# Power.net
KiCad netlist of a schematic drawn in Altium Designer
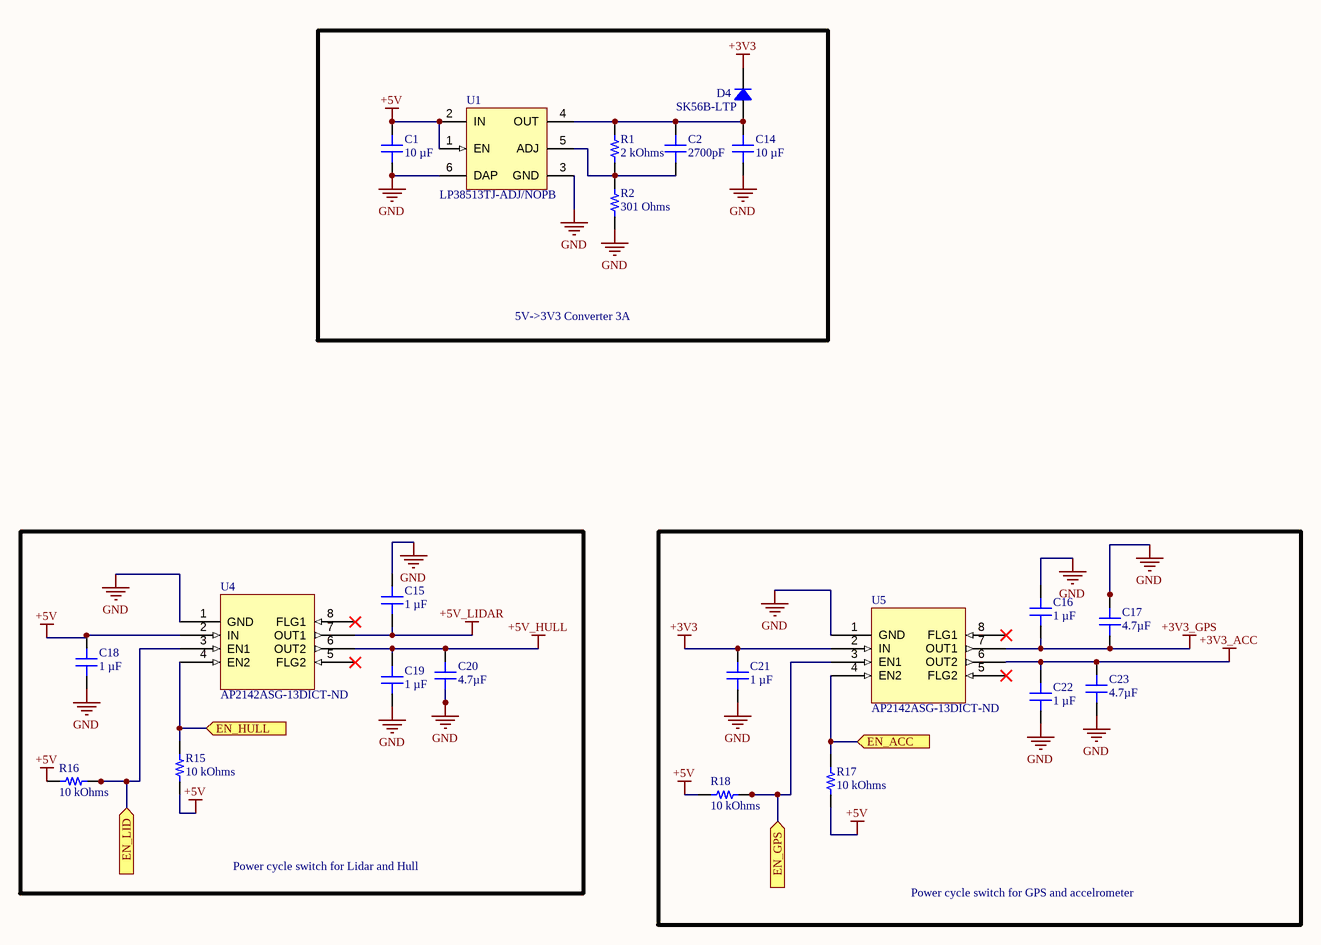
[diagram p0: Power.SchDoc]

(export (version "E")
  (design (tool "Eeschema 10.0.6"))
  (components
    (comp (ref "C1")
      (value "10 µF")
      (footprint "CAP 0805_2012")
      (description "CAP CER 10UF 16V X5R 0805")
      (fields
        (field (name "PART NUMBER") "CGA4J1X5R1C106K125AC")
        (field (name "MANUFACTURER") "TDK Corporation")
      )
      (libsource (lib "Celestial Altium Library - altium_library") (part "Capacitor"))
    )
    (comp (ref "C2")
      (value "2700pF")
      (footprint "CAP 0603_1608")
      (description "CAP CER 2700PF 50V X7R 0603")
      (fields (field (name "PART NUMBER") "06035C272KAT2A") (field (name "MANUFACTURER") "AVX Corporation"))
      (libsource (lib "Celestial Altium Library - altium_library") (part "Capacitor"))
    )
    (comp (ref "C14")
      (value "10 µF")
      (footprint "CAP 0805_2012")
      (description "CAP CER 10UF 16V X5R 0805")
      (fields
        (field (name "PART NUMBER") "CGA4J1X5R1C106K125AC")
        (field (name "MANUFACTURER") "TDK Corporation")
      )
      (libsource (lib "Celestial Altium Library - altium_library") (part "Capacitor"))
    )
    (comp (ref "C15")
      (value "1 µF")
      (footprint "CAP 0603_1608")
      (description "CAP CER 1UF 16V X7R 0603")
      (fields (field (name "PART NUMBER") "CM105X7R105K16ATH") (field (name "MANUFACTURER") "KYOCERA AVX"))
      (libsource (lib "Celestial Altium Library - altium_library") (part "Capacitor"))
    )
    (comp (ref "C16")
      (value "1 µF")
      (footprint "CAP 0603_1608")
      (description "CAP CER 1UF 16V X7R 0603")
      (fields (field (name "PART NUMBER") "CM105X7R105K16ATH") (field (name "MANUFACTURER") "KYOCERA AVX"))
      (libsource (lib "Celestial Altium Library - altium_library") (part "Capacitor"))
    )
    (comp (ref "C17")
      (value "4.7µF")
      (footprint "CAP 0805_2012")
      (description "CAP CER 4.7UF 10V X7R 0805")
      (fields (field (name "PART NUMBER") "0805ZC475MAT2A") (field (name "MANUFACTURER") "AVX Corporation"))
      (libsource (lib "Celestial Altium Library - altium_library") (part "Capacitor"))
    )
    (comp (ref "C18")
      (value "1 µF")
      (footprint "CAP 0603_1608")
      (description "CAP CER 1UF 16V X7R 0603")
      (fields (field (name "PART NUMBER") "CM105X7R105K16ATH") (field (name "MANUFACTURER") "KYOCERA AVX"))
      (libsource (lib "Celestial Altium Library - altium_library") (part "Capacitor"))
    )
    (comp (ref "C19")
      (value "1 µF")
      (footprint "CAP 0603_1608")
      (description "CAP CER 1UF 16V X7R 0603")
      (fields (field (name "PART NUMBER") "CM105X7R105K16ATH") (field (name "MANUFACTURER") "KYOCERA AVX"))
      (libsource (lib "Celestial Altium Library - altium_library") (part "Capacitor"))
    )
    (comp (ref "C20")
      (value "4.7µF")
      (footprint "CAP 0805_2012")
      (description "CAP CER 4.7UF 10V X7R 0805")
      (fields (field (name "PART NUMBER") "0805ZC475MAT2A") (field (name "MANUFACTURER") "AVX Corporation"))
      (libsource (lib "Celestial Altium Library - altium_library") (part "Capacitor"))
    )
    (comp (ref "C21")
      (value "1 µF")
      (footprint "CAP 0603_1608")
      (description "CAP CER 1UF 16V X7R 0603")
      (fields (field (name "PART NUMBER") "CM105X7R105K16ATH") (field (name "MANUFACTURER") "KYOCERA AVX"))
      (libsource (lib "Celestial Altium Library - altium_library") (part "Capacitor"))
    )
    (comp (ref "C22")
      (value "1 µF")
      (footprint "CAP 0603_1608")
      (description "CAP CER 1UF 16V X7R 0603")
      (fields (field (name "PART NUMBER") "CM105X7R105K16ATH") (field (name "MANUFACTURER") "KYOCERA AVX"))
      (libsource (lib "Celestial Altium Library - altium_library") (part "Capacitor"))
    )
    (comp (ref "C23")
      (value "4.7µF")
      (footprint "CAP 0805_2012")
      (description "CAP CER 4.7UF 10V X7R 0805")
      (fields (field (name "PART NUMBER") "0805ZC475MAT2A") (field (name "MANUFACTURER") "AVX Corporation"))
      (libsource (lib "Celestial Altium Library - altium_library") (part "Capacitor"))
    )
    (comp (ref "D4")
      (value "SK56B-LTP")
      (footprint "DO214AA SMB")
      (description "DIODE SCHOTTKY 60V 5A DO214AA")
      (fields (field (name "MANUFACTURER") "Micro Commercial Co"))
      (libsource (lib "Celestial Altium Library - altium_library") (part "Diode"))
    )
    (comp (ref "R1")
      (value "2 kOhms")
      (footprint "RES 0603_1608")
      (description "RES 2K OHM 1% 1/10W 0603")
      (fields
        (field (name "PART NUMBER") "RMCF0603FT2K00")
        (field (name "MANUFACTURER") "Stackpole Electronics Inc")
      )
      (libsource (lib "Celestial Altium Library - altium_library") (part "Resistor"))
    )
    (comp (ref "R2")
      (value "301 Ohms")
      (footprint "RES 0603_1608")
      (description "RES 301 OHM 1% 1/10W 0603")
      (fields
        (field (name "PART NUMBER") "RMCF0603FT301R")
        (field (name "MANUFACTURER") "Stackpole Electronics Inc")
      )
      (libsource (lib "Celestial Altium Library - altium_library") (part "Resistor"))
    )
    (comp (ref "R15")
      (value "10 kOhms")
      (footprint "RES 0603_1608")
      (description "RES SMD 10K OHM 1% 1/10W 0603")
      (fields (field (name "PART NUMBER") "RT0603FRE0710KL") (field (name "MANUFACTURER") "Yageo"))
      (libsource (lib "Celestial Altium Library - altium_library") (part "Resistor"))
    )
    (comp (ref "R16")
      (value "10 kOhms")
      (footprint "RES 0603_1608")
      (description "RES SMD 10K OHM 1% 1/10W 0603")
      (fields (field (name "PART NUMBER") "RT0603FRE0710KL") (field (name "MANUFACTURER") "Yageo"))
      (libsource (lib "Celestial Altium Library - altium_library") (part "Resistor"))
    )
    (comp (ref "R17")
      (value "10 kOhms")
      (footprint "RES 0603_1608")
      (description "RES SMD 10K OHM 1% 1/10W 0603")
      (fields (field (name "PART NUMBER") "RT0603FRE0710KL") (field (name "MANUFACTURER") "Yageo"))
      (libsource (lib "Celestial Altium Library - altium_library") (part "Resistor"))
    )
    (comp (ref "R18")
      (value "10 kOhms")
      (footprint "RES 0603_1608")
      (description "RES SMD 10K OHM 1% 1/10W 0603")
      (fields (field (name "PART NUMBER") "RT0603FRE0710KL") (field (name "MANUFACTURER") "Yageo"))
      (libsource (lib "Celestial Altium Library - altium_library") (part "Resistor"))
    )
    (comp (ref "U1")
      (value "LP38513TJ-ADJ/NOPB")
      (footprint "NDQ0005A_M")
      (fields (field (name "MANUFACTURER") "Texas Instruments"))
      (libsource (lib "Altium Content Vault") (part "PM-REG-LP38513-SIL6A"))
    )
    (comp (ref "U4")
      (value "AP2142ASG-13DICT-ND")
      (footprint "SOP127P600X175-8N")
      (description "AP2142A Series 5.5 V 0.5 A Dual Channel Current-Limited Power Switch - SOIC-8")
      (libsource (lib "Americas- Environmental Engineering Club- University of Victoria") (part "AP2142ASG-13DICT-ND-Symbol-1"))
    )
    (comp (ref "U5")
      (value "AP2142ASG-13DICT-ND")
      (footprint "SOP127P600X175-8N")
      (description "AP2142A Series 5.5 V 0.5 A Dual Channel Current-Limited Power Switch - SOIC-8")
      (libsource (lib "Americas- Environmental Engineering Club- University of Victoria") (part "AP2142ASG-13DICT-ND-Symbol-1"))
    )
  )
  (nets
    (net (code "1") (name "+3V3") (class "Default")
      (node (ref "C21") (pin "1") (pinfunction "1_1") (pintype "passive"))
      (node (ref "D4") (pin "2") (pinfunction "2_2") (pintype "passive"))
      (node (ref "U5") (pin "2") (pinfunction "IN_2") (pintype "input"))
    )
    (net (code "2") (name "+3V3_ACC") (class "Default")
      (node (ref "C22") (pin "2") (pinfunction "2_2") (pintype "passive"))
      (node (ref "C23") (pin "2") (pinfunction "2_2") (pintype "passive"))
      (node (ref "U5") (pin "6") (pinfunction "OUT2_6") (pintype "output"))
    )
    (net (code "3") (name "+3V3_GPS") (class "Default")
      (node (ref "C16") (pin "1") (pinfunction "1_1") (pintype "passive"))
      (node (ref "C17") (pin "2") (pinfunction "2_2") (pintype "passive"))
      (node (ref "U5") (pin "7") (pinfunction "OUT1_7") (pintype "output"))
    )
    (net (code "4") (name "+5V") (class "Default")
      (node (ref "C1") (pin "2") (pinfunction "2_2") (pintype "passive"))
      (node (ref "C18") (pin "1") (pinfunction "1_1") (pintype "passive"))
      (node (ref "R15") (pin "2") (pinfunction "2_2") (pintype "passive"))
      (node (ref "R16") (pin "2") (pinfunction "2_2") (pintype "passive"))
      (node (ref "R17") (pin "2") (pinfunction "2_2") (pintype "passive"))
      (node (ref "R18") (pin "2") (pinfunction "2_2") (pintype "passive"))
      (node (ref "U1") (pin "1") (pinfunction "EN_1") (pintype "input"))
      (node (ref "U1") (pin "2") (pinfunction "IN_2") (pintype "power_in"))
      (node (ref "U4") (pin "2") (pinfunction "IN_2") (pintype "input"))
    )
    (net (code "5") (name "+5V_HULL") (class "Default")
      (node (ref "C19") (pin "2") (pinfunction "2_2") (pintype "passive"))
      (node (ref "C20") (pin "2") (pinfunction "2_2") (pintype "passive"))
      (node (ref "U4") (pin "6") (pinfunction "OUT2_6") (pintype "output"))
    )
    (net (code "6") (name "+5V_LIDAR") (class "Default")
      (node (ref "C15") (pin "1") (pinfunction "1_1") (pintype "passive"))
      (node (ref "U4") (pin "7") (pinfunction "OUT1_7") (pintype "output"))
    )
    (net (code "7") (name "/EN_ACC") (class "Default")
      (node (ref "R17") (pin "1") (pinfunction "1_1") (pintype "passive"))
      (node (ref "U5") (pin "4") (pinfunction "EN2_4") (pintype "input"))
    )
    (net (code "8") (name "/EN_GPS") (class "Default")
      (node (ref "R18") (pin "1") (pinfunction "1_1") (pintype "passive"))
      (node (ref "U5") (pin "3") (pinfunction "EN1_3") (pintype "input"))
    )
    (net (code "9") (name "/EN_HULL") (class "Default")
      (node (ref "R15") (pin "1") (pinfunction "1_1") (pintype "passive"))
      (node (ref "U4") (pin "4") (pinfunction "EN2_4") (pintype "input"))
    )
    (net (code "10") (name "/EN_LID") (class "Default")
      (node (ref "R16") (pin "1") (pinfunction "1_1") (pintype "passive"))
      (node (ref "U4") (pin "3") (pinfunction "EN1_3") (pintype "input"))
    )
    (net (code "11") (name "GND") (class "Default")
      (node (ref "C1") (pin "1") (pinfunction "1_1") (pintype "passive"))
      (node (ref "C14") (pin "1") (pinfunction "1_1") (pintype "passive"))
      (node (ref "C15") (pin "2") (pinfunction "2_2") (pintype "passive"))
      (node (ref "C16") (pin "2") (pinfunction "2_2") (pintype "passive"))
      (node (ref "C17") (pin "1") (pinfunction "1_1") (pintype "passive"))
      (node (ref "C18") (pin "2") (pinfunction "2_2") (pintype "passive"))
      (node (ref "C19") (pin "1") (pinfunction "1_1") (pintype "passive"))
      (node (ref "C20") (pin "1") (pinfunction "1_1") (pintype "passive"))
      (node (ref "C21") (pin "2") (pinfunction "2_2") (pintype "passive"))
      (node (ref "C22") (pin "1") (pinfunction "1_1") (pintype "passive"))
      (node (ref "C23") (pin "1") (pinfunction "1_1") (pintype "passive"))
      (node (ref "R2") (pin "1") (pinfunction "1_1") (pintype "passive"))
      (node (ref "U1") (pin "3") (pinfunction "GND_3") (pintype "power_in"))
      (node (ref "U1") (pin "6") (pinfunction "DAP_6") (pintype "passive"))
      (node (ref "U4") (pin "1") (pinfunction "GND_1") (pintype "power_in"))
      (node (ref "U5") (pin "1") (pinfunction "GND_1") (pintype "power_in"))
    )
    (net (code "12") (name "Net-(U1-ADJ)") (class "Default")
      (node (ref "C2") (pin "1") (pinfunction "1_1") (pintype "passive"))
      (node (ref "R1") (pin "1") (pinfunction "1_1") (pintype "passive"))
      (node (ref "R2") (pin "2") (pinfunction "2_2") (pintype "passive"))
      (node (ref "U1") (pin "5") (pinfunction "ADJ_5") (pintype "passive"))
    )
    (net (code "13") (name "Net-(U1-OUT)") (class "Default")
      (node (ref "C14") (pin "2") (pinfunction "2_2") (pintype "passive"))
      (node (ref "C2") (pin "2") (pinfunction "2_2") (pintype "passive"))
      (node (ref "D4") (pin "1") (pinfunction "1_1") (pintype "passive"))
      (node (ref "R1") (pin "2") (pinfunction "2_2") (pintype "passive"))
      (node (ref "U1") (pin "4") (pinfunction "OUT_4") (pintype "power_in"))
    )
    (net (code "14") (name "unconnected-(U4-FLG1-Pad8)") (class "Default")
      (node (ref "U4") (pin "8") (pinfunction "FLG1_8") (pintype "input+no_connect"))
    )
    (net (code "15") (name "unconnected-(U4-FLG2-Pad5)") (class "Default")
      (node (ref "U4") (pin "5") (pinfunction "FLG2_5") (pintype "input+no_connect"))
    )
    (net (code "16") (name "unconnected-(U5-FLG1-Pad8)") (class "Default")
      (node (ref "U5") (pin "8") (pinfunction "FLG1_8") (pintype "input+no_connect"))
    )
    (net (code "17") (name "unconnected-(U5-FLG2-Pad5)") (class "Default")
      (node (ref "U5") (pin "5") (pinfunction "FLG2_5") (pintype "input+no_connect"))
    )
  )
)
